# HA_LCD1_14_V1_1.net
KiCad netlist of a schematic drawn in EAGLE
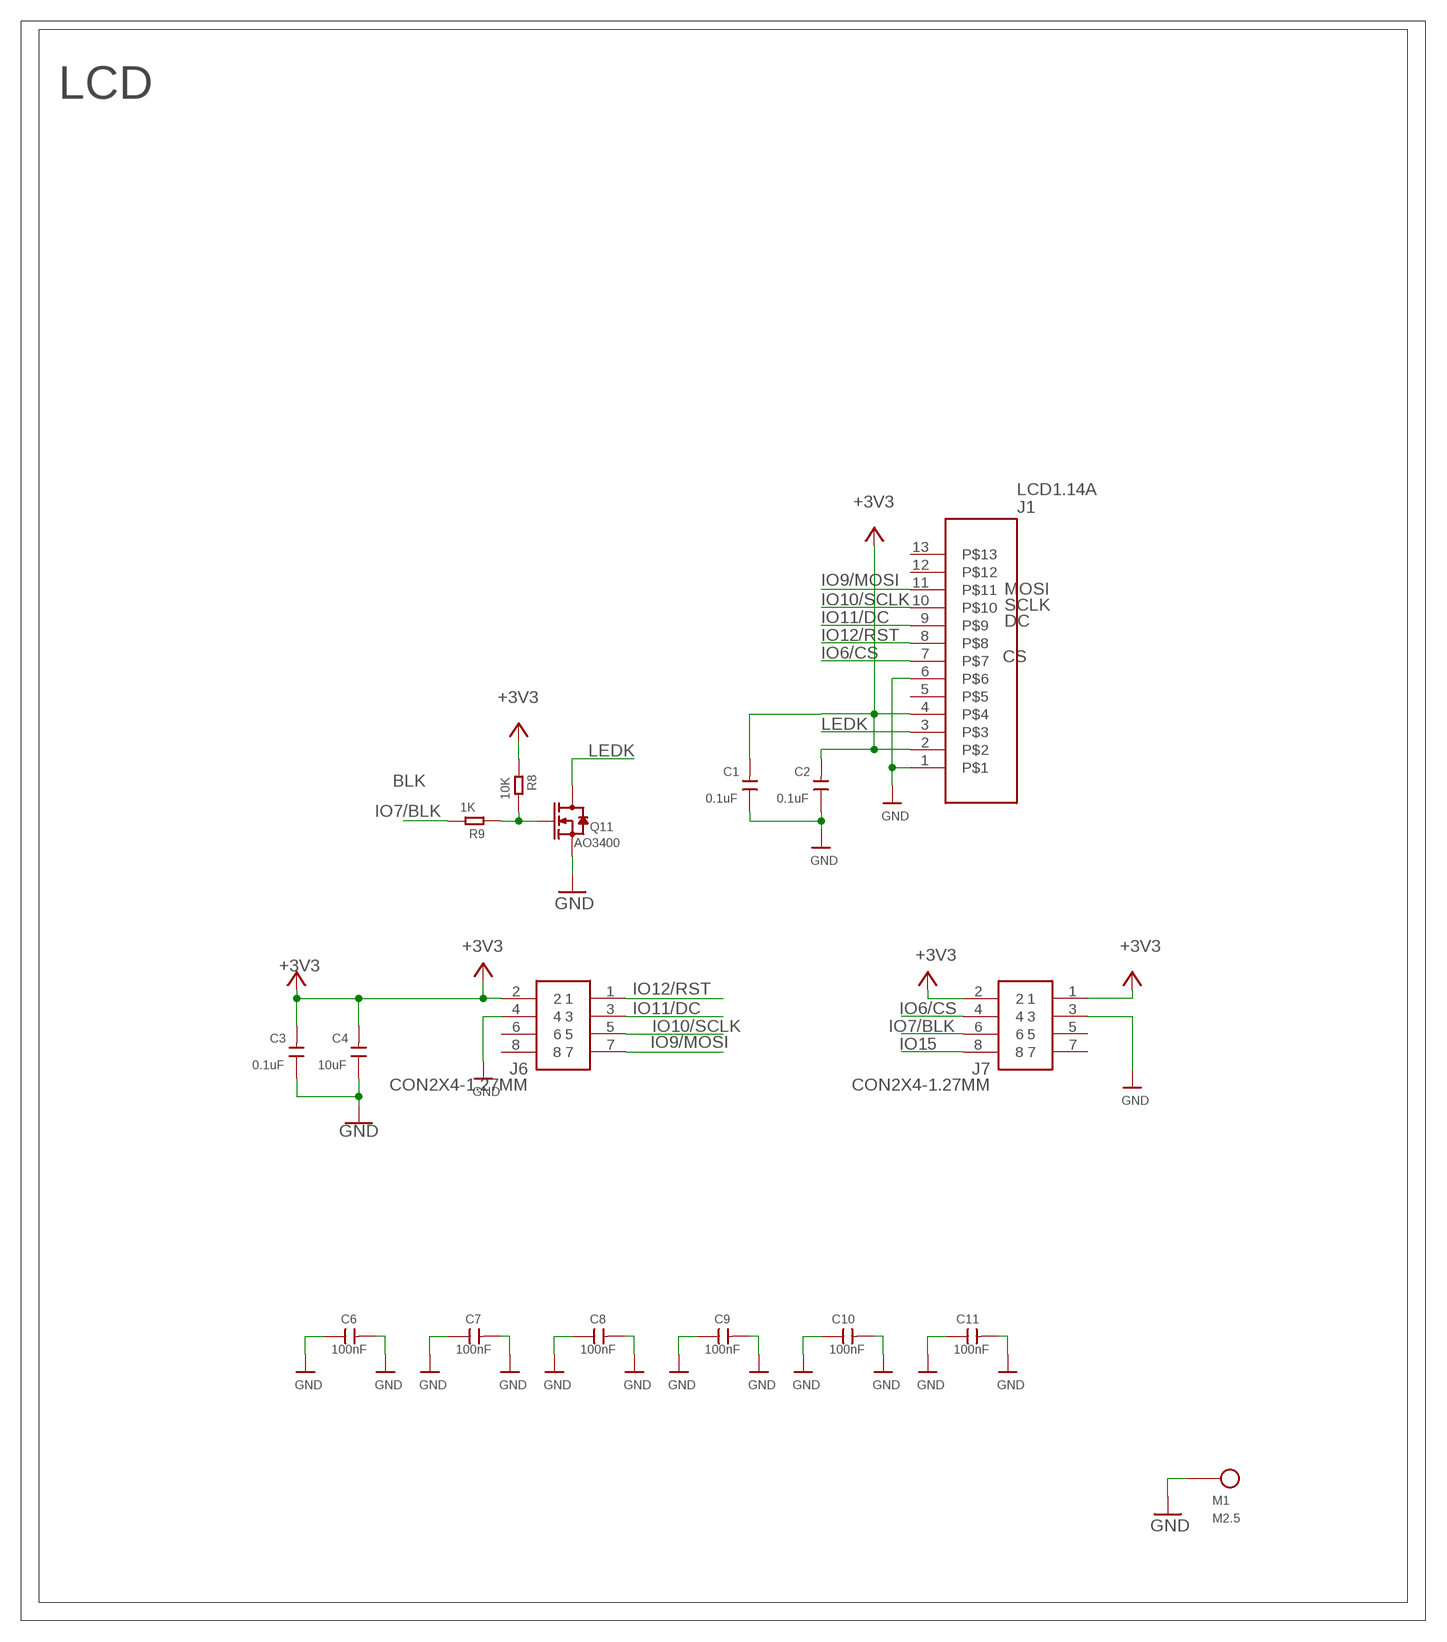
[diagram p0: schematic, sheet 1]

(export (version "E")
  (design (tool "Eeschema 10.0.6"))
  (components
    (comp (ref "C1")
      (value "0.1uF")
      (footprint "eagle-import:DISCRETE_C0402")
      (libsource (lib "eagle-import") (part "DISCRETE_C-0402"))
    )
    (comp (ref "C2")
      (value "0.1uF")
      (footprint "eagle-import:DISCRETE_C0402")
      (libsource (lib "eagle-import") (part "DISCRETE_C-0402"))
    )
    (comp (ref "C3")
      (value "0.1uF")
      (footprint "eagle-import:DISCRETE_C0402")
      (libsource (lib "eagle-import") (part "DISCRETE_C-0402"))
    )
    (comp (ref "C4")
      (value "10uF")
      (footprint "eagle-import:DISCRETE_C0402")
      (libsource (lib "eagle-import") (part "DISCRETE_C-0402"))
    )
    (comp (ref "C6")
      (value "100nF")
      (footprint "eagle-import:0603")
      (libsource (lib "eagle-import") (part "C-0603"))
    )
    (comp (ref "C7")
      (value "100nF")
      (footprint "eagle-import:0603")
      (libsource (lib "eagle-import") (part "C-0603"))
    )
    (comp (ref "C8")
      (value "100nF")
      (footprint "eagle-import:0603")
      (libsource (lib "eagle-import") (part "C-0603"))
    )
    (comp (ref "C9")
      (value "100nF")
      (footprint "eagle-import:0603")
      (libsource (lib "eagle-import") (part "C-0603"))
    )
    (comp (ref "C10")
      (value "100nF")
      (footprint "eagle-import:0603")
      (libsource (lib "eagle-import") (part "C-0603"))
    )
    (comp (ref "C11")
      (value "100nF")
      (footprint "eagle-import:0603")
      (libsource (lib "eagle-import") (part "C-0603"))
    )
    (comp (ref "J1")
      (value "LCD1.14A")
      (footprint "eagle-import:LCD1.14A")
      (libsource (lib "eagle-import") (part "LCD1.14A"))
    )
    (comp (ref "J6")
      (value "CON2X4-1.27MM")
      (footprint "eagle-import:CON2X4-1.27MM")
      (libsource (lib "eagle-import") (part "CON2X4-1.27MM"))
    )
    (comp (ref "J7")
      (value "CON2X4-1.27MM")
      (footprint "eagle-import:CON2X4-1.27MM")
      (libsource (lib "eagle-import") (part "CON2X4-1.27MM"))
    )
    (comp (ref "M1")
      (value "M2.5")
      (footprint "eagle-import:M2.5")
      (libsource (lib "eagle-import") (part "M2.5"))
    )
    (comp (ref "Q11")
      (value "AO3400")
      (footprint "eagle-import:SOT23")
      (libsource (lib "eagle-import") (part "MOSFET-N'SOT23'"))
    )
    (comp (ref "R8")
      (value "10K")
      (footprint "eagle-import:DISCRETE_R0402")
      (libsource (lib "eagle-import") (part "DISCRETE_R-0402"))
    )
    (comp (ref "R9")
      (value "1K")
      (footprint "eagle-import:DISCRETE_R0402")
      (libsource (lib "eagle-import") (part "DISCRETE_R-0402"))
    )
  )
  (nets
    (net (code "1") (name "+3V3") (class "Default")
      (node (ref "C1") (pin "2") (pinfunction "2_2") (pintype "passive"))
      (node (ref "C2") (pin "2") (pinfunction "2_2") (pintype "passive"))
      (node (ref "C3") (pin "2") (pinfunction "2_2") (pintype "passive"))
      (node (ref "C4") (pin "2") (pinfunction "2_2") (pintype "passive"))
      (node (ref "J1") (pin "2") (pinfunction "P$2_2") (pintype "bidirectional"))
      (node (ref "J1") (pin "4") (pinfunction "P$4_4") (pintype "bidirectional"))
      (node (ref "J6") (pin "2") (pinfunction "2_2") (pintype "bidirectional"))
      (node (ref "J7") (pin "1") (pinfunction "1_1") (pintype "bidirectional"))
      (node (ref "J7") (pin "2") (pinfunction "2_2") (pintype "bidirectional"))
      (node (ref "R8") (pin "1") (pinfunction "1_1") (pintype "passive"))
    )
    (net (code "2") (name "/IO6{slash}CS") (class "Default")
      (node (ref "J1") (pin "7") (pinfunction "P$7_7") (pintype "bidirectional"))
      (node (ref "J7") (pin "4") (pinfunction "4_4") (pintype "bidirectional"))
    )
    (net (code "3") (name "/IO7{slash}BLK") (class "Default")
      (node (ref "J7") (pin "6") (pinfunction "6_6") (pintype "bidirectional"))
      (node (ref "R9") (pin "2") (pinfunction "2_2") (pintype "passive"))
    )
    (net (code "4") (name "/IO9{slash}MOSI") (class "Default")
      (node (ref "J1") (pin "11") (pinfunction "P$11_11") (pintype "bidirectional"))
      (node (ref "J6") (pin "7") (pinfunction "7_7") (pintype "bidirectional"))
    )
    (net (code "5") (name "/IO10{slash}SCLK") (class "Default")
      (node (ref "J1") (pin "10") (pinfunction "P$10_10") (pintype "bidirectional"))
      (node (ref "J6") (pin "5") (pinfunction "5_5") (pintype "bidirectional"))
    )
    (net (code "6") (name "/IO11{slash}DC") (class "Default")
      (node (ref "J1") (pin "9") (pinfunction "P$9_9") (pintype "bidirectional"))
      (node (ref "J6") (pin "3") (pinfunction "3_3") (pintype "bidirectional"))
    )
    (net (code "7") (name "/IO12{slash}RST") (class "Default")
      (node (ref "J1") (pin "8") (pinfunction "P$8_8") (pintype "bidirectional"))
      (node (ref "J6") (pin "1") (pinfunction "1_1") (pintype "bidirectional"))
    )
    (net (code "8") (name "/IO15") (class "Default")
      (node (ref "J7") (pin "8") (pinfunction "8_8") (pintype "bidirectional"))
    )
    (net (code "9") (name "/LEDK") (class "Default")
      (node (ref "J1") (pin "3") (pinfunction "P$3_3") (pintype "bidirectional"))
      (node (ref "Q11") (pin "3") (pinfunction "D_3") (pintype "passive"))
    )
    (net (code "10") (name "GND") (class "Default")
      (node (ref "C1") (pin "1") (pinfunction "1_1") (pintype "passive"))
      (node (ref "C10") (pin "1") (pinfunction "1_1") (pintype "passive"))
      (node (ref "C10") (pin "2") (pinfunction "2_2") (pintype "passive"))
      (node (ref "C11") (pin "1") (pinfunction "1_1") (pintype "passive"))
      (node (ref "C11") (pin "2") (pinfunction "2_2") (pintype "passive"))
      (node (ref "C2") (pin "1") (pinfunction "1_1") (pintype "passive"))
      (node (ref "C3") (pin "1") (pinfunction "1_1") (pintype "passive"))
      (node (ref "C4") (pin "1") (pinfunction "1_1") (pintype "passive"))
      (node (ref "C6") (pin "1") (pinfunction "1_1") (pintype "passive"))
      (node (ref "C6") (pin "2") (pinfunction "2_2") (pintype "passive"))
      (node (ref "C7") (pin "1") (pinfunction "1_1") (pintype "passive"))
      (node (ref "C7") (pin "2") (pinfunction "2_2") (pintype "passive"))
      (node (ref "C8") (pin "1") (pinfunction "1_1") (pintype "passive"))
      (node (ref "C8") (pin "2") (pinfunction "2_2") (pintype "passive"))
      (node (ref "C9") (pin "1") (pinfunction "1_1") (pintype "passive"))
      (node (ref "C9") (pin "2") (pinfunction "2_2") (pintype "passive"))
      (node (ref "J1") (pin "1") (pinfunction "P$1_1") (pintype "bidirectional"))
      (node (ref "J1") (pin "6") (pinfunction "P$6_6") (pintype "bidirectional"))
      (node (ref "J6") (pin "4") (pinfunction "4_4") (pintype "bidirectional"))
      (node (ref "J7") (pin "3") (pinfunction "3_3") (pintype "bidirectional"))
      (node (ref "M1") (pin "1") (pinfunction "P$1_1") (pintype "bidirectional"))
      (node (ref "Q11") (pin "2") (pinfunction "S_2") (pintype "passive"))
    )
    (net (code "11") (name "Net-(Q11-G)") (class "Default")
      (node (ref "Q11") (pin "1") (pinfunction "G_1") (pintype "passive"))
      (node (ref "R8") (pin "2") (pinfunction "2_2") (pintype "passive"))
      (node (ref "R9") (pin "1") (pinfunction "1_1") (pintype "passive"))
    )
    (net (code "12") (name "unconnected-(J1-P$5-Pad5)") (class "Default")
      (node (ref "J1") (pin "5") (pinfunction "P$5_5") (pintype "bidirectional"))
    )
    (net (code "13") (name "unconnected-(J1-P$12-Pad12)") (class "Default")
      (node (ref "J1") (pin "12") (pinfunction "P$12_12") (pintype "bidirectional"))
    )
    (net (code "14") (name "unconnected-(J1-P$13-Pad13)") (class "Default")
      (node (ref "J1") (pin "13") (pinfunction "P$13_13") (pintype "bidirectional"))
    )
    (net (code "15") (name "unconnected-(J6-Pad6)") (class "Default")
      (node (ref "J6") (pin "6") (pinfunction "6_6") (pintype "bidirectional"))
    )
    (net (code "16") (name "unconnected-(J6-Pad8)") (class "Default")
      (node (ref "J6") (pin "8") (pinfunction "8_8") (pintype "bidirectional"))
    )
    (net (code "17") (name "unconnected-(J7-Pad5)") (class "Default")
      (node (ref "J7") (pin "5") (pinfunction "5_5") (pintype "bidirectional"))
    )
    (net (code "18") (name "unconnected-(J7-Pad7)") (class "Default")
      (node (ref "J7") (pin "7") (pinfunction "7_7") (pintype "bidirectional"))
    )
  )
)
